# HackRPI-Badge.net
KiCad netlist of a schematic drawn in EAGLE
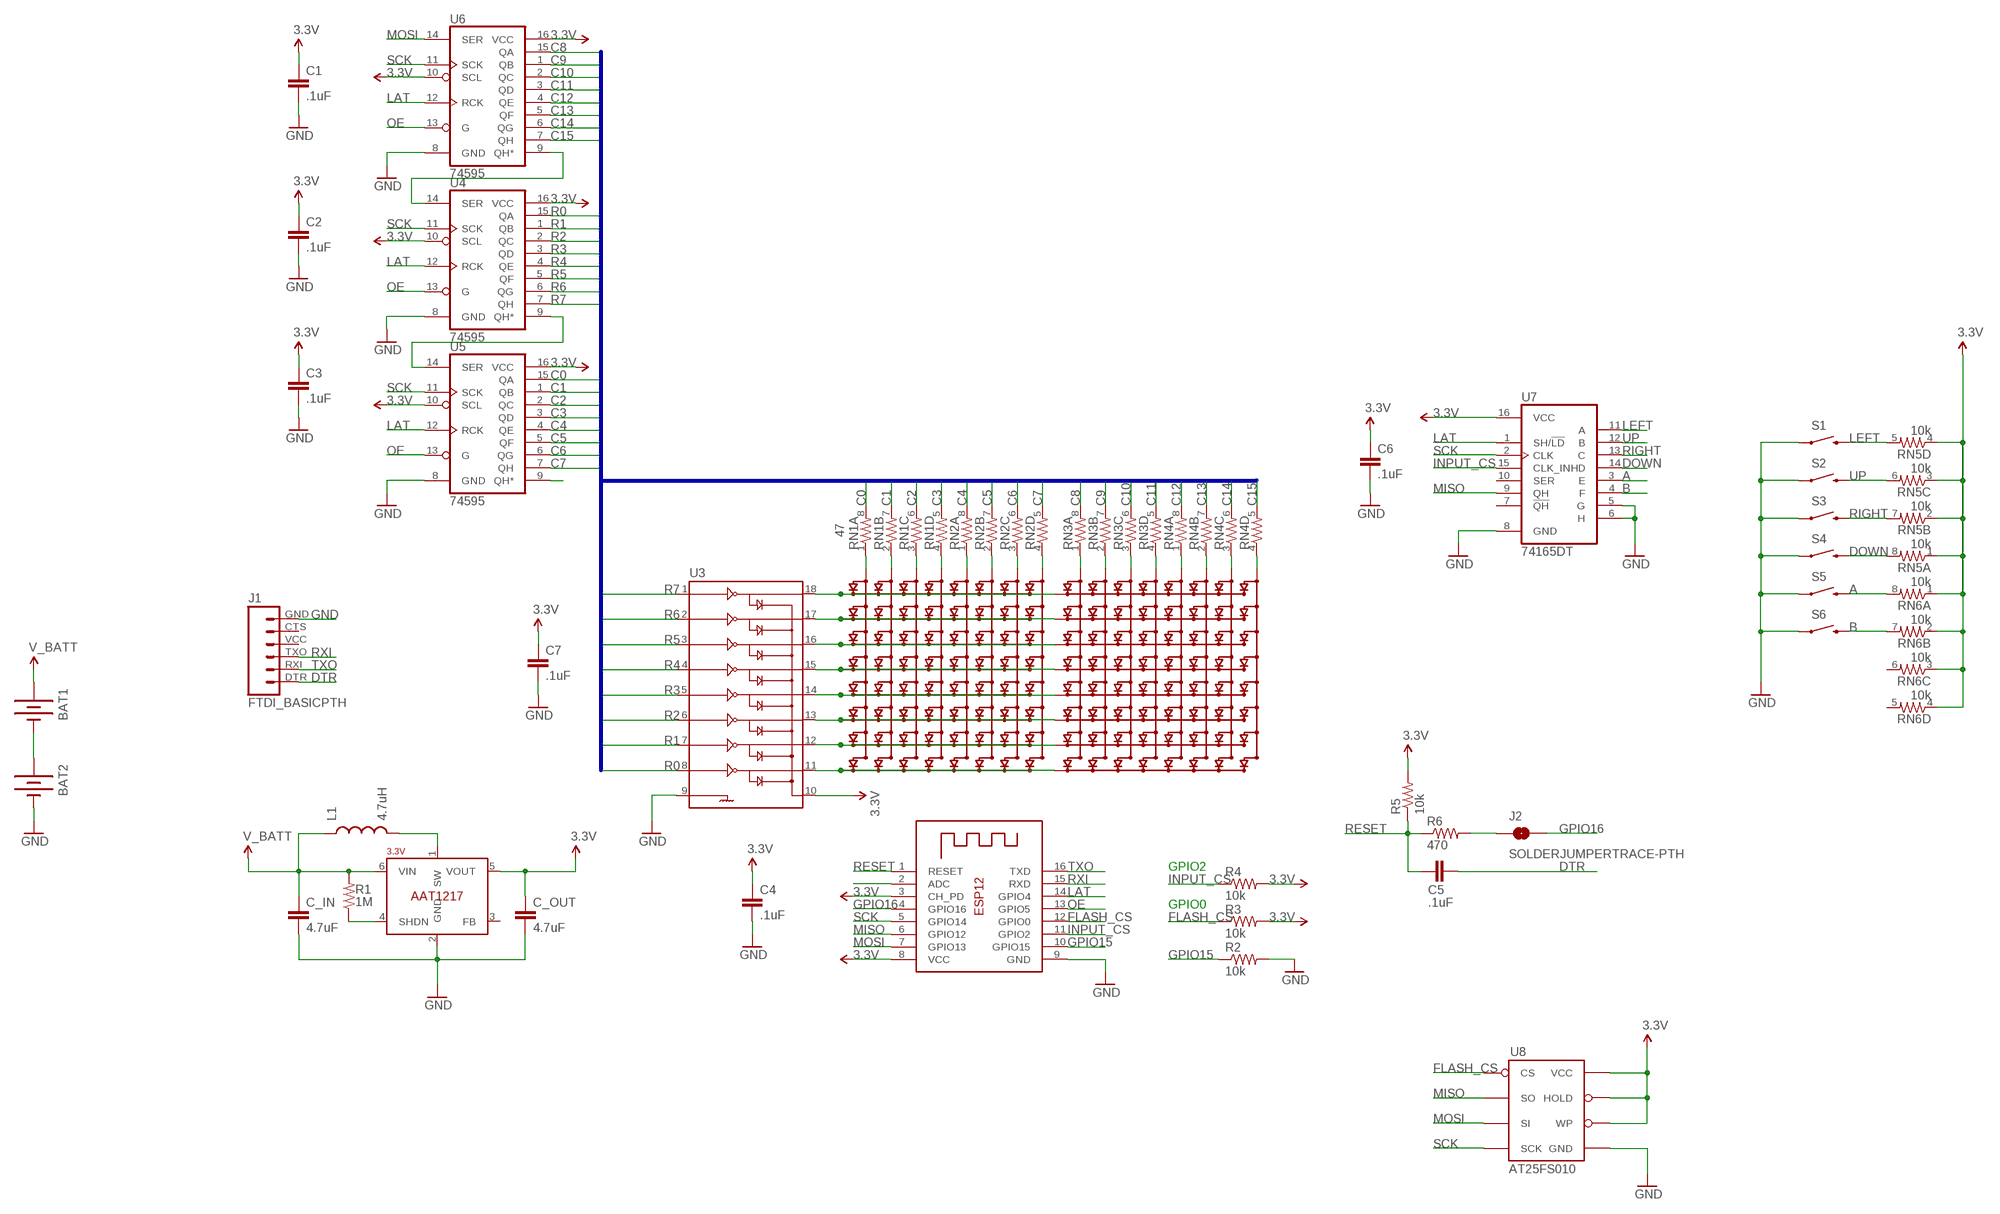
[diagram p0: schematic, sheet 1]

(export (version "E")
  (design (tool "Eeschema 10.0.6"))
  (components
    (comp (ref "BAT1")
      (value "BATTERYAAA")
      (footprint "eagle-import:BATTERY-AAA")
      (libsource (lib "eagle-import") (part "BATTERYAAA"))
    )
    (comp (ref "BAT2")
      (value "BATTERYAAA")
      (footprint "eagle-import:BATTERY-AAA")
      (libsource (lib "eagle-import") (part "BATTERYAAA"))
    )
    (comp (ref "C1")
      (value ".1uF")
      (footprint "eagle-import:0603-CAP")
      (libsource (lib "eagle-import") (part "CAP0603-CAP"))
    )
    (comp (ref "C2")
      (value ".1uF")
      (footprint "eagle-import:0603-CAP")
      (libsource (lib "eagle-import") (part "CAP0603-CAP"))
    )
    (comp (ref "C3")
      (value ".1uF")
      (footprint "eagle-import:0603-CAP")
      (libsource (lib "eagle-import") (part "CAP0603-CAP"))
    )
    (comp (ref "C4")
      (value ".1uF")
      (footprint "eagle-import:0603-CAP")
      (libsource (lib "eagle-import") (part "CAP0603-CAP"))
    )
    (comp (ref "C5")
      (value ".1uF")
      (footprint "eagle-import:0603-CAP")
      (libsource (lib "eagle-import") (part "CAP0603-CAP"))
    )
    (comp (ref "C6")
      (value ".1uF")
      (footprint "eagle-import:0603-CAP")
      (libsource (lib "eagle-import") (part "CAP0603-CAP"))
    )
    (comp (ref "C7")
      (value ".1uF")
      (footprint "eagle-import:0603-CAP")
      (libsource (lib "eagle-import") (part "CAP0603-CAP"))
    )
    (comp (ref "C_IN")
      (value "4.7uF")
      (footprint "eagle-import:0805")
      (libsource (lib "eagle-import") (part "CAP0805"))
    )
    (comp (ref "C_OUT")
      (value "4.7uF")
      (footprint "eagle-import:0805")
      (libsource (lib "eagle-import") (part "CAP0805"))
    )
    (comp (ref "J1")
      (value "FTDI_BASICPTH")
      (footprint "eagle-import:FTDI_BASIC")
      (libsource (lib "eagle-import") (part "FTDI_BASICPTH"))
    )
    (comp (ref "J2")
      (value "SOLDERJUMPERTRACE-PTH")
      (footprint "eagle-import:SJ_2S-TRACE-PTH")
      (libsource (lib "eagle-import") (part "SOLDERJUMPERTRACE-PTH"))
    )
    (comp (ref "L1")
      (value "4.7uH")
      (footprint "eagle-import:1007")
      (libsource (lib "eagle-import") (part "INDUCTOR1007"))
    )
    (comp (ref "LED_LEFT")
      (value "8X8LEDMATRIX_COLUMN_CATHODELDM-13488MI")
      (footprint "eagle-import:32MM_LEDMATRIX")
      (libsource (lib "eagle-import") (part "8X8LEDMATRIX_COLUMN_CATHODELDM-13488MI"))
    )
    (comp (ref "LEF_RIGHT")
      (value "8X8LEDMATRIX_COLUMN_CATHODELDM-13488MI")
      (footprint "eagle-import:32MM_LEDMATRIX")
      (libsource (lib "eagle-import") (part "8X8LEDMATRIX_COLUMN_CATHODELDM-13488MI"))
    )
    (comp (ref "R1")
      (value "1M")
      (footprint "eagle-import:0603-RES")
      (libsource (lib "eagle-import") (part "RESISTOR0603"))
    )
    (comp (ref "R2")
      (value "10k")
      (footprint "eagle-import:0603-RES")
      (libsource (lib "eagle-import") (part "RESISTOR0603"))
    )
    (comp (ref "R3")
      (value "10k")
      (footprint "eagle-import:0603-RES")
      (libsource (lib "eagle-import") (part "RESISTOR0603"))
    )
    (comp (ref "R4")
      (value "10k")
      (footprint "eagle-import:0603-RES")
      (libsource (lib "eagle-import") (part "RESISTOR0603"))
    )
    (comp (ref "R5")
      (value "10k")
      (footprint "eagle-import:0603-RES")
      (libsource (lib "eagle-import") (part "RESISTOR0603"))
    )
    (comp (ref "R6")
      (value "470")
      (footprint "eagle-import:0603-RES")
      (libsource (lib "eagle-import") (part "RESISTOR0603"))
    )
    (comp (ref "RN1")
      (value "47")
      (footprint "eagle-import:0603-ARV")
      (libsource (lib "eagle-import") (part "RESISTOR-ARRAY0603-ARV"))
    )
    (comp (ref "RN2")
      (value "47")
      (footprint "eagle-import:0603-ARV")
      (libsource (lib "eagle-import") (part "RESISTOR-ARRAY0603-ARV"))
    )
    (comp (ref "RN3")
      (value "47")
      (footprint "eagle-import:0603-ARV")
      (libsource (lib "eagle-import") (part "RESISTOR-ARRAY0603-ARV"))
    )
    (comp (ref "RN4")
      (value "47")
      (footprint "eagle-import:0603-ARV")
      (libsource (lib "eagle-import") (part "RESISTOR-ARRAY0603-ARV"))
    )
    (comp (ref "RN5")
      (value "10k")
      (footprint "eagle-import:0603-ARV")
      (libsource (lib "eagle-import") (part "RESISTOR-ARRAY0603-ARV"))
    )
    (comp (ref "RN6")
      (value "10k")
      (footprint "eagle-import:0603-ARV")
      (libsource (lib "eagle-import") (part "RESISTOR-ARRAY0603-ARV"))
    )
    (comp (ref "S1")
      (value "SWITCH-MOMENTARY-2PTH")
      (footprint "eagle-import:TACTILE-PTH")
      (libsource (lib "eagle-import") (part "SWITCH-MOMENTARY-2PTH"))
    )
    (comp (ref "S2")
      (value "SWITCH-MOMENTARY-2PTH")
      (footprint "eagle-import:TACTILE-PTH")
      (libsource (lib "eagle-import") (part "SWITCH-MOMENTARY-2PTH"))
    )
    (comp (ref "S3")
      (value "SWITCH-MOMENTARY-2PTH")
      (footprint "eagle-import:TACTILE-PTH")
      (libsource (lib "eagle-import") (part "SWITCH-MOMENTARY-2PTH"))
    )
    (comp (ref "S4")
      (value "SWITCH-MOMENTARY-2PTH")
      (footprint "eagle-import:TACTILE-PTH")
      (libsource (lib "eagle-import") (part "SWITCH-MOMENTARY-2PTH"))
    )
    (comp (ref "S5")
      (value "SWITCH-MOMENTARY-2PTH")
      (footprint "eagle-import:TACTILE-PTH")
      (libsource (lib "eagle-import") (part "SWITCH-MOMENTARY-2PTH"))
    )
    (comp (ref "S6")
      (value "SWITCH-MOMENTARY-2PTH")
      (footprint "eagle-import:TACTILE-PTH")
      (libsource (lib "eagle-import") (part "SWITCH-MOMENTARY-2PTH"))
    )
    (comp (ref "U1")
      (value "ESP-12")
      (footprint "eagle-import:ESP-12")
      (libsource (lib "eagle-import") (part "ESP-12"))
    )
    (comp (ref "U2")
      (value "3.3V")
      (footprint "eagle-import:SOT23-6")
      (libsource (lib "eagle-import") (part "AAT1217"))
    )
    (comp (ref "U3")
      (value "ULN2803SOICW")
      (footprint "eagle-import:SO18L")
      (libsource (lib "eagle-import") (part "ULN2803SOICW"))
    )
    (comp (ref "U4")
      (value "74595")
      (footprint "eagle-import:TSSOP16")
      (libsource (lib "eagle-import") (part "74595"))
    )
    (comp (ref "U5")
      (value "74595")
      (footprint "eagle-import:TSSOP16")
      (libsource (lib "eagle-import") (part "74595"))
    )
    (comp (ref "U6")
      (value "74595")
      (footprint "eagle-import:TSSOP16")
      (libsource (lib "eagle-import") (part "74595"))
    )
    (comp (ref "U7")
      (value "74165DT")
      (footprint "eagle-import:TSSOP16")
      (libsource (lib "eagle-import") (part "74165DT"))
    )
    (comp (ref "U8")
      (value "AT25FS010")
      (footprint "eagle-import:SO08WIDE")
      (libsource (lib "eagle-import") (part "AT25FS010"))
    )
  )
  (nets
    (net (code "1") (name "/A") (class "Default")
      (node (ref "RN6") (pin "8") (pinfunction "2_8") (pintype "passive"))
      (node (ref "S5") (pin "3") (pinfunction "2_3") (pintype "passive"))
      (node (ref "U7") (pin "3") (pinfunction "E_3") (pintype "tri_state"))
    )
    (net (code "2") (name "/B") (class "Default")
      (node (ref "RN6") (pin "7") (pinfunction "2_7") (pintype "passive"))
      (node (ref "S6") (pin "3") (pinfunction "2_3") (pintype "passive"))
      (node (ref "U7") (pin "4") (pinfunction "F_4") (pintype "tri_state"))
    )
    (net (code "3") (name "/C0") (class "Default")
      (node (ref "RN1") (pin "8") (pinfunction "2_8") (pintype "passive"))
      (node (ref "U5") (pin "15") (pinfunction "QA_15") (pintype "tri_state"))
    )
    (net (code "4") (name "/C1") (class "Default")
      (node (ref "RN1") (pin "7") (pinfunction "2_7") (pintype "passive"))
      (node (ref "U5") (pin "1") (pinfunction "QB_1") (pintype "tri_state"))
    )
    (net (code "5") (name "/C2") (class "Default")
      (node (ref "RN1") (pin "6") (pinfunction "2_6") (pintype "passive"))
      (node (ref "U5") (pin "2") (pinfunction "QC_2") (pintype "tri_state"))
    )
    (net (code "6") (name "/C3") (class "Default")
      (node (ref "RN1") (pin "5") (pinfunction "2_5") (pintype "passive"))
      (node (ref "U5") (pin "3") (pinfunction "QD_3") (pintype "tri_state"))
    )
    (net (code "7") (name "/C4") (class "Default")
      (node (ref "RN2") (pin "8") (pinfunction "2_8") (pintype "passive"))
      (node (ref "U5") (pin "4") (pinfunction "QE_4") (pintype "tri_state"))
    )
    (net (code "8") (name "/C5") (class "Default")
      (node (ref "RN2") (pin "7") (pinfunction "2_7") (pintype "passive"))
      (node (ref "U5") (pin "5") (pinfunction "QF_5") (pintype "tri_state"))
    )
    (net (code "9") (name "/C6") (class "Default")
      (node (ref "RN2") (pin "6") (pinfunction "2_6") (pintype "passive"))
      (node (ref "U5") (pin "6") (pinfunction "QG_6") (pintype "tri_state"))
    )
    (net (code "10") (name "/C7") (class "Default")
      (node (ref "RN2") (pin "5") (pinfunction "2_5") (pintype "passive"))
      (node (ref "U5") (pin "7") (pinfunction "QH_7") (pintype "tri_state"))
    )
    (net (code "11") (name "/C8") (class "Default")
      (node (ref "RN3") (pin "8") (pinfunction "2_8") (pintype "passive"))
      (node (ref "U6") (pin "15") (pinfunction "QA_15") (pintype "tri_state"))
    )
    (net (code "12") (name "/C9") (class "Default")
      (node (ref "RN3") (pin "7") (pinfunction "2_7") (pintype "passive"))
      (node (ref "U6") (pin "1") (pinfunction "QB_1") (pintype "tri_state"))
    )
    (net (code "13") (name "/C10") (class "Default")
      (node (ref "RN3") (pin "6") (pinfunction "2_6") (pintype "passive"))
      (node (ref "U6") (pin "2") (pinfunction "QC_2") (pintype "tri_state"))
    )
    (net (code "14") (name "/C11") (class "Default")
      (node (ref "RN3") (pin "5") (pinfunction "2_5") (pintype "passive"))
      (node (ref "U6") (pin "3") (pinfunction "QD_3") (pintype "tri_state"))
    )
    (net (code "15") (name "/C12") (class "Default")
      (node (ref "RN4") (pin "8") (pinfunction "2_8") (pintype "passive"))
      (node (ref "U6") (pin "4") (pinfunction "QE_4") (pintype "tri_state"))
    )
    (net (code "16") (name "/C13") (class "Default")
      (node (ref "RN4") (pin "7") (pinfunction "2_7") (pintype "passive"))
      (node (ref "U6") (pin "5") (pinfunction "QF_5") (pintype "tri_state"))
    )
    (net (code "17") (name "/C14") (class "Default")
      (node (ref "RN4") (pin "6") (pinfunction "2_6") (pintype "passive"))
      (node (ref "U6") (pin "6") (pinfunction "QG_6") (pintype "tri_state"))
    )
    (net (code "18") (name "/C15") (class "Default")
      (node (ref "RN4") (pin "5") (pinfunction "2_5") (pintype "passive"))
      (node (ref "U6") (pin "7") (pinfunction "QH_7") (pintype "tri_state"))
    )
    (net (code "19") (name "/DOWN") (class "Default")
      (node (ref "RN5") (pin "8") (pinfunction "2_8") (pintype "passive"))
      (node (ref "S4") (pin "3") (pinfunction "2_3") (pintype "passive"))
      (node (ref "U7") (pin "14") (pinfunction "D_14") (pintype "tri_state"))
    )
    (net (code "20") (name "/DTR") (class "Default")
      (node (ref "C5") (pin "2") (pinfunction "2_2") (pintype "passive"))
      (node (ref "J1") (pin "DTR") (pinfunction "1_DTR") (pintype "passive"))
    )
    (net (code "21") (name "/FLASH_CS") (class "Default")
      (node (ref "R3") (pin "1") (pinfunction "1_1") (pintype "passive"))
      (node (ref "U1") (pin "12") (pinfunction "GPIO0_12") (pintype "bidirectional"))
      (node (ref "U8") (pin "1") (pinfunction "CS_1") (pintype "bidirectional"))
    )
    (net (code "22") (name "/GPIO15") (class "Default")
      (node (ref "R2") (pin "1") (pinfunction "1_1") (pintype "passive"))
      (node (ref "U1") (pin "10") (pinfunction "GPIO15_10") (pintype "bidirectional"))
    )
    (net (code "23") (name "/GPIO16") (class "Default")
      (node (ref "J2") (pin "2") (pinfunction "2_2") (pintype "passive"))
      (node (ref "U1") (pin "4") (pinfunction "GPIO16_4") (pintype "bidirectional"))
    )
    (net (code "24") (name "/INPUT_CS") (class "Default")
      (node (ref "R4") (pin "1") (pinfunction "1_1") (pintype "passive"))
      (node (ref "U1") (pin "11") (pinfunction "GPIO2_11") (pintype "bidirectional"))
      (node (ref "U7") (pin "15") (pinfunction "CLK_INH_15") (pintype "input"))
    )
    (net (code "25") (name "/LAT") (class "Default")
      (node (ref "U1") (pin "14") (pinfunction "GPIO4_14") (pintype "bidirectional"))
      (node (ref "U4") (pin "12") (pinfunction "RCK_12") (pintype "input"))
      (node (ref "U5") (pin "12") (pinfunction "RCK_12") (pintype "input"))
      (node (ref "U6") (pin "12") (pinfunction "RCK_12") (pintype "input"))
      (node (ref "U7") (pin "1") (pinfunction "SH/~{LD}_1") (pintype "input"))
    )
    (net (code "26") (name "/LEFT") (class "Default")
      (node (ref "RN5") (pin "5") (pinfunction "2_5") (pintype "passive"))
      (node (ref "S1") (pin "3") (pinfunction "2_3") (pintype "passive"))
      (node (ref "U7") (pin "11") (pinfunction "A_11") (pintype "tri_state"))
    )
    (net (code "27") (name "/MISO") (class "Default")
      (node (ref "U1") (pin "6") (pinfunction "GPIO12_6") (pintype "bidirectional"))
      (node (ref "U7") (pin "9") (pinfunction "QH_9") (pintype "tri_state"))
      (node (ref "U8") (pin "2") (pinfunction "SO_2") (pintype "bidirectional"))
    )
    (net (code "28") (name "/MOSI") (class "Default")
      (node (ref "U1") (pin "7") (pinfunction "GPIO13_7") (pintype "bidirectional"))
      (node (ref "U6") (pin "14") (pinfunction "SER_14") (pintype "input"))
      (node (ref "U8") (pin "5") (pinfunction "SI_5") (pintype "bidirectional"))
    )
    (net (code "29") (name "/OE") (class "Default")
      (node (ref "U1") (pin "13") (pinfunction "GPIO5_13") (pintype "bidirectional"))
      (node (ref "U4") (pin "13") (pinfunction "G_13") (pintype "input"))
      (node (ref "U5") (pin "13") (pinfunction "G_13") (pintype "input"))
      (node (ref "U6") (pin "13") (pinfunction "G_13") (pintype "input"))
    )
    (net (code "30") (name "/R0") (class "Default")
      (node (ref "U3") (pin "8") (pinfunction "8_8") (pintype "bidirectional"))
      (node (ref "U4") (pin "15") (pinfunction "QA_15") (pintype "tri_state"))
    )
    (net (code "31") (name "/R1") (class "Default")
      (node (ref "U3") (pin "7") (pinfunction "7_7") (pintype "bidirectional"))
      (node (ref "U4") (pin "1") (pinfunction "QB_1") (pintype "tri_state"))
    )
    (net (code "32") (name "/R2") (class "Default")
      (node (ref "U3") (pin "6") (pinfunction "6_6") (pintype "bidirectional"))
      (node (ref "U4") (pin "2") (pinfunction "QC_2") (pintype "tri_state"))
    )
    (net (code "33") (name "/R3") (class "Default")
      (node (ref "U3") (pin "5") (pinfunction "5_5") (pintype "bidirectional"))
      (node (ref "U4") (pin "3") (pinfunction "QD_3") (pintype "tri_state"))
    )
    (net (code "34") (name "/R4") (class "Default")
      (node (ref "U3") (pin "4") (pinfunction "4_4") (pintype "bidirectional"))
      (node (ref "U4") (pin "4") (pinfunction "QE_4") (pintype "tri_state"))
    )
    (net (code "35") (name "/R5") (class "Default")
      (node (ref "U3") (pin "3") (pinfunction "3_3") (pintype "bidirectional"))
      (node (ref "U4") (pin "5") (pinfunction "QF_5") (pintype "tri_state"))
    )
    (net (code "36") (name "/R6") (class "Default")
      (node (ref "U3") (pin "2") (pinfunction "2_2") (pintype "bidirectional"))
      (node (ref "U4") (pin "6") (pinfunction "QG_6") (pintype "tri_state"))
    )
    (net (code "37") (name "/R7") (class "Default")
      (node (ref "U3") (pin "1") (pinfunction "1_1") (pintype "bidirectional"))
      (node (ref "U4") (pin "7") (pinfunction "QH_7") (pintype "tri_state"))
    )
    (net (code "38") (name "/RESET") (class "Default")
      (node (ref "C5") (pin "1") (pinfunction "1_1") (pintype "passive"))
      (node (ref "R5") (pin "1") (pinfunction "1_1") (pintype "passive"))
      (node (ref "R6") (pin "1") (pinfunction "1_1") (pintype "passive"))
      (node (ref "U1") (pin "1") (pinfunction "RESET_1") (pintype "input"))
    )
    (net (code "39") (name "/RIGHT") (class "Default")
      (node (ref "RN5") (pin "7") (pinfunction "2_7") (pintype "passive"))
      (node (ref "S3") (pin "3") (pinfunction "2_3") (pintype "passive"))
      (node (ref "U7") (pin "13") (pinfunction "C_13") (pintype "tri_state"))
    )
    (net (code "40") (name "/RXI") (class "Default")
      (node (ref "J1") (pin "TXO") (pinfunction "3_TXO") (pintype "passive"))
      (node (ref "U1") (pin "15") (pinfunction "RXD_15") (pintype "input"))
    )
    (net (code "41") (name "/SCK") (class "Default")
      (node (ref "U1") (pin "5") (pinfunction "GPIO14_5") (pintype "bidirectional"))
      (node (ref "U4") (pin "11") (pinfunction "SCK_11") (pintype "input"))
      (node (ref "U5") (pin "11") (pinfunction "SCK_11") (pintype "input"))
      (node (ref "U6") (pin "11") (pinfunction "SCK_11") (pintype "input"))
      (node (ref "U7") (pin "2") (pinfunction "CLK_2") (pintype "input"))
      (node (ref "U8") (pin "6") (pinfunction "SCK_6") (pintype "bidirectional"))
    )
    (net (code "42") (name "/TXO") (class "Default")
      (node (ref "J1") (pin "RXI") (pinfunction "2_RXI") (pintype "passive"))
      (node (ref "U1") (pin "16") (pinfunction "TXD_16") (pintype "output"))
    )
    (net (code "43") (name "/UP") (class "Default")
      (node (ref "RN5") (pin "6") (pinfunction "2_6") (pintype "passive"))
      (node (ref "S2") (pin "3") (pinfunction "2_3") (pintype "passive"))
      (node (ref "U7") (pin "12") (pinfunction "B_12") (pintype "tri_state"))
    )
    (net (code "44") (name "3.3V") (class "Default")
      (node (ref "C1") (pin "1") (pinfunction "1_1") (pintype "passive"))
      (node (ref "C2") (pin "1") (pinfunction "1_1") (pintype "passive"))
      (node (ref "C3") (pin "1") (pinfunction "1_1") (pintype "passive"))
      (node (ref "C4") (pin "1") (pinfunction "1_1") (pintype "passive"))
      (node (ref "C6") (pin "1") (pinfunction "1_1") (pintype "passive"))
      (node (ref "C7") (pin "1") (pinfunction "1_1") (pintype "passive"))
      (node (ref "C_OUT") (pin "1") (pinfunction "1_1") (pintype "passive"))
      (node (ref "R3") (pin "2") (pinfunction "2_2") (pintype "passive"))
      (node (ref "R4") (pin "2") (pinfunction "2_2") (pintype "passive"))
      (node (ref "R5") (pin "2") (pinfunction "2_2") (pintype "passive"))
      (node (ref "RN5") (pin "1") (pinfunction "1_1") (pintype "passive"))
      (node (ref "RN5") (pin "2") (pinfunction "1_2") (pintype "passive"))
      (node (ref "RN5") (pin "3") (pinfunction "1_3") (pintype "passive"))
      (node (ref "RN5") (pin "4") (pinfunction "1_4") (pintype "passive"))
      (node (ref "RN6") (pin "1") (pinfunction "1_1") (pintype "passive"))
      (node (ref "RN6") (pin "2") (pinfunction "1_2") (pintype "passive"))
      (node (ref "RN6") (pin "3") (pinfunction "1_3") (pintype "passive"))
      (node (ref "RN6") (pin "4") (pinfunction "1_4") (pintype "passive"))
      (node (ref "U1") (pin "3") (pinfunction "CH_PD_3") (pintype "input"))
      (node (ref "U1") (pin "8") (pinfunction "VCC_8") (pintype "power_in"))
      (node (ref "U2") (pin "5") (pinfunction "VOUT_5") (pintype "power_in"))
      (node (ref "U3") (pin "10") (pinfunction "10_10") (pintype "bidirectional"))
      (node (ref "U4") (pin "10") (pinfunction "SCL_10") (pintype "input"))
      (node (ref "U4") (pin "16") (pinfunction "VCC_16") (pintype "power_in"))
      (node (ref "U5") (pin "10") (pinfunction "SCL_10") (pintype "input"))
      (node (ref "U5") (pin "16") (pinfunction "VCC_16") (pintype "power_in"))
      (node (ref "U6") (pin "10") (pinfunction "SCL_10") (pintype "input"))
      (node (ref "U6") (pin "16") (pinfunction "VCC_16") (pintype "power_in"))
      (node (ref "U7") (pin "16") (pinfunction "VCC_16") (pintype "power_in"))
      (node (ref "U8") (pin "3") (pinfunction "WP_3") (pintype "bidirectional"))
      (node (ref "U8") (pin "7") (pinfunction "HOLD_7") (pintype "bidirectional"))
      (node (ref "U8") (pin "8") (pinfunction "VCC_8") (pintype "bidirectional"))
    )
    (net (code "45") (name "GND") (class "Default")
      (node (ref "BAT2") (pin "GND@1") (pinfunction "-_GND@1") (pintype "power_in"))
      (node (ref "C1") (pin "2") (pinfunction "2_2") (pintype "passive"))
      (node (ref "C2") (pin "2") (pinfunction "2_2") (pintype "passive"))
      (node (ref "C3") (pin "2") (pinfunction "2_2") (pintype "passive"))
      (node (ref "C4") (pin "2") (pinfunction "2_2") (pintype "passive"))
      (node (ref "C6") (pin "2") (pinfunction "2_2") (pintype "passive"))
      (node (ref "C7") (pin "2") (pinfunction "2_2") (pintype "passive"))
      (node (ref "C_IN") (pin "2") (pinfunction "2_2") (pintype "passive"))
      (node (ref "C_OUT") (pin "2") (pinfunction "2_2") (pintype "passive"))
      (node (ref "J1") (pin "GND") (pinfunction "6_GND") (pintype "passive"))
      (node (ref "R2") (pin "2") (pinfunction "2_2") (pintype "passive"))
      (node (ref "S1") (pin "1") (pinfunction "1_1") (pintype "passive"))
      (node (ref "S2") (pin "1") (pinfunction "1_1") (pintype "passive"))
      (node (ref "S3") (pin "1") (pinfunction "1_1") (pintype "passive"))
      (node (ref "S4") (pin "1") (pinfunction "1_1") (pintype "passive"))
      (node (ref "S5") (pin "1") (pinfunction "1_1") (pintype "passive"))
      (node (ref "S6") (pin "1") (pinfunction "1_1") (pintype "passive"))
      (node (ref "U1") (pin "9") (pinfunction "GND_9") (pintype "power_in"))
      (node (ref "U2") (pin "2") (pinfunction "GND_2") (pintype "power_in"))
      (node (ref "U3") (pin "9") (pinfunction "9_9") (pintype "bidirectional"))
      (node (ref "U4") (pin "8") (pinfunction "GND_8") (pintype "power_in"))
      (node (ref "U5") (pin "8") (pinfunction "GND_8") (pintype "power_in"))
      (node (ref "U6") (pin "8") (pinfunction "GND_8") (pintype "power_in"))
      (node (ref "U7") (pin "5") (pinfunction "G_5") (pintype "tri_state"))
      (node (ref "U7") (pin "6") (pinfunction "H_6") (pintype "tri_state"))
      (node (ref "U7") (pin "8") (pinfunction "GND_8") (pintype "power_in"))
      (node (ref "U8") (pin "4") (pinfunction "GND_4") (pintype "bidirectional"))
    )
    (net (code "46") (name "Net-(BAT1--)") (class "Default")
      (node (ref "BAT1") (pin "GND@1") (pinfunction "-_GND@1") (pintype "power_in"))
      (node (ref "BAT2") (pin "PWR@1") (pinfunction "+_PWR@1") (pintype "power_in"))
    )
    (net (code "47") (name "Net-(J2-Pad1)") (class "Default")
      (node (ref "J2") (pin "1") (pinfunction "1_1") (pintype "passive"))
      (node (ref "R6") (pin "2") (pinfunction "2_2") (pintype "passive"))
    )
    (net (code "48") (name "Net-(LED_LEFT-C1)") (class "Default")
      (node (ref "LED_LEFT") (pin "13") (pinfunction "C1_13") (pintype "bidirectional"))
      (node (ref "RN1") (pin "1") (pinfunction "1_1") (pintype "passive"))
    )
    (net (code "49") (name "Net-(LED_LEFT-C2)") (class "Default")
      (node (ref "LED_LEFT") (pin "3") (pinfunction "C2_3") (pintype "bidirectional"))
      (node (ref "RN1") (pin "2") (pinfunction "1_2") (pintype "passive"))
    )
    (net (code "50") (name "Net-(LED_LEFT-C3)") (class "Default")
      (node (ref "LED_LEFT") (pin "4") (pinfunction "C3_4") (pintype "bidirectional"))
      (node (ref "RN1") (pin "3") (pinfunction "1_3") (pintype "passive"))
    )
    (net (code "51") (name "Net-(LED_LEFT-C4)") (class "Default")
      (node (ref "LED_LEFT") (pin "10") (pinfunction "C4_10") (pintype "bidirectional"))
      (node (ref "RN1") (pin "4") (pinfunction "1_4") (pintype "passive"))
    )
    (net (code "52") (name "Net-(LED_LEFT-C5)") (class "Default")
      (node (ref "LED_LEFT") (pin "6") (pinfunction "C5_6") (pintype "bidirectional"))
      (node (ref "RN2") (pin "1") (pinfunction "1_1") (pintype "passive"))
    )
    (net (code "53") (name "Net-(LED_LEFT-C6)") (class "Default")
      (node (ref "LED_LEFT") (pin "11") (pinfunction "C6_11") (pintype "bidirectional"))
      (node (ref "RN2") (pin "2") (pinfunction "1_2") (pintype "passive"))
    )
    (net (code "54") (name "Net-(LED_LEFT-C7)") (class "Default")
      (node (ref "LED_LEFT") (pin "15") (pinfunction "C7_15") (pintype "bidirectional"))
      (node (ref "RN2") (pin "3") (pinfunction "1_3") (pintype "passive"))
    )
    (net (code "55") (name "Net-(LED_LEFT-C8)") (class "Default")
      (node (ref "LED_LEFT") (pin "16") (pinfunction "C8_16") (pintype "bidirectional"))
      (node (ref "RN2") (pin "4") (pinfunction "1_4") (pintype "passive"))
    )
    (net (code "56") (name "Net-(LED_LEFT-R1)") (class "Default")
      (node (ref "LED_LEFT") (pin "9") (pinfunction "R1_9") (pintype "bidirectional"))
      (node (ref "LEF_RIGHT") (pin "9") (pinfunction "R1_9") (pintype "bidirectional"))
      (node (ref "U3") (pin "18") (pinfunction "18_18") (pintype "bidirectional"))
    )
    (net (code "57") (name "Net-(LED_LEFT-R2)") (class "Default")
      (node (ref "LED_LEFT") (pin "14") (pinfunction "R2_14") (pintype "bidirectional"))
      (node (ref "LEF_RIGHT") (pin "14") (pinfunction "R2_14") (pintype "bidirectional"))
      (node (ref "U3") (pin "17") (pinfunction "17_17") (pintype "bidirectional"))
    )
    (net (code "58") (name "Net-(LED_LEFT-R3)") (class "Default")
      (node (ref "LED_LEFT") (pin "8") (pinfunction "R3_8") (pintype "bidirectional"))
      (node (ref "LEF_RIGHT") (pin "8") (pinfunction "R3_8") (pintype "bidirectional"))
      (node (ref "U3") (pin "16") (pinfunction "16_16") (pintype "bidirectional"))
    )
    (net (code "59") (name "Net-(LED_LEFT-R4)") (class "Default")
      (node (ref "LED_LEFT") (pin "12") (pinfunction "R4_12") (pintype "bidirectional"))
      (node (ref "LEF_RIGHT") (pin "12") (pinfunction "R4_12") (pintype "bidirectional"))
      (node (ref "U3") (pin "15") (pinfunction "15_15") (pintype "bidirectional"))
    )
    (net (code "60") (name "Net-(LED_LEFT-R5)") (class "Default")
      (node (ref "LED_LEFT") (pin "1") (pinfunction "R5_1") (pintype "bidirectional"))
      (node (ref "LEF_RIGHT") (pin "1") (pinfunction "R5_1") (pintype "bidirectional"))
      (node (ref "U3") (pin "14") (pinfunction "14_14") (pintype "bidirectional"))
    )
    (net (code "61") (name "Net-(LED_LEFT-R6)") (class "Default")
      (node (ref "LED_LEFT") (pin "7") (pinfunction "R6_7") (pintype "bidirectional"))
      (node (ref "LEF_RIGHT") (pin "7") (pinfunction "R6_7") (pintype "bidirectional"))
      (node (ref "U3") (pin "13") (pinfunction "13_13") (pintype "bidirectional"))
    )
    (net (code "62") (name "Net-(LED_LEFT-R7)") (class "Default")
      (node (ref "LED_LEFT") (pin "2") (pinfunction "R7_2") (pintype "bidirectional"))
      (node (ref "LEF_RIGHT") (pin "2") (pinfunction "R7_2") (pintype "bidirectional"))
      (node (ref "U3") (pin "12") (pinfunction "12_12") (pintype "bidirectional"))
    )
    (net (code "63") (name "Net-(LED_LEFT-R8)") (class "Default")
      (node (ref "LED_LEFT") (pin "5") (pinfunction "R8_5") (pintype "bidirectional"))
      (node (ref "LEF_RIGHT") (pin "5") (pinfunction "R8_5") (pintype "bidirectional"))
      (node (ref "U3") (pin "11") (pinfunction "11_11") (pintype "bidirectional"))
    )
    (net (code "64") (name "Net-(LEF_RIGHT-C1)") (class "Default")
      (node (ref "LEF_RIGHT") (pin "13") (pinfunction "C1_13") (pintype "bidirectional"))
      (node (ref "RN3") (pin "1") (pinfunction "1_1") (pintype "passive"))
    )
    (net (code "65") (name "Net-(LEF_RIGHT-C2)") (class "Default")
      (node (ref "LEF_RIGHT") (pin "3") (pinfunction "C2_3") (pintype "bidirectional"))
      (node (ref "RN3") (pin "2") (pinfunction "1_2") (pintype "passive"))
    )
    (net (code "66") (name "Net-(LEF_RIGHT-C3)") (class "Default")
      (node (ref "LEF_RIGHT") (pin "4") (pinfunction "C3_4") (pintype "bidirectional"))
      (node (ref "RN3") (pin "3") (pinfunction "1_3") (pintype "passive"))
    )
    (net (code "67") (name "Net-(LEF_RIGHT-C4)") (class "Default")
      (node (ref "LEF_RIGHT") (pin "10") (pinfunction "C4_10") (pintype "bidirectional"))
      (node (ref "RN3") (pin "4") (pinfunction "1_4") (pintype "passive"))
    )
    (net (code "68") (name "Net-(LEF_RIGHT-C5)") (class "Default")
      (node (ref "LEF_RIGHT") (pin "6") (pinfunction "C5_6") (pintype "bidirectional"))
      (node (ref "RN4") (pin "1") (pinfunction "1_1") (pintype "passive"))
    )
    (net (code "69") (name "Net-(LEF_RIGHT-C6)") (class "Default")
      (node (ref "LEF_RIGHT") (pin "11") (pinfunction "C6_11") (pintype "bidirectional"))
      (node (ref "RN4") (pin "2") (pinfunction "1_2") (pintype "passive"))
    )
    (net (code "70") (name "Net-(LEF_RIGHT-C7)") (class "Default")
      (node (ref "LEF_RIGHT") (pin "15") (pinfunction "C7_15") (pintype "bidirectional"))
      (node (ref "RN4") (pin "3") (pinfunction "1_3") (pintype "passive"))
    )
    (net (code "71") (name "Net-(LEF_RIGHT-C8)") (class "Default")
      (node (ref "LEF_RIGHT") (pin "16") (pinfunction "C8_16") (pintype "bidirectional"))
      (node (ref "RN4") (pin "4") (pinfunction "1_4") (pintype "passive"))
    )
    (net (code "72") (name "Net-(U2-SHDN)") (class "Default")
      (node (ref "R1") (pin "1") (pinfunction "1_1") (pintype "passive"))
      (node (ref "U2") (pin "4") (pinfunction "SHDN_4") (pintype "input"))
    )
    (net (code "73") (name "Net-(U2-SW)") (class "Default")
      (node (ref "L1") (pin "2") (pinfunction "2_2") (pintype "passive"))
      (node (ref "U2") (pin "1") (pinfunction "SW_1") (pintype "input"))
    )
    (net (code "74") (name "Net-(U4-QH*)") (class "Default")
      (node (ref "U4") (pin "9") (pinfunction "QH*_9") (pintype "tri_state"))
      (node (ref "U5") (pin "14") (pinfunction "SER_14") (pintype "input"))
    )
    (net (code "75") (name "Net-(U4-SER)") (class "Default")
      (node (ref "U4") (pin "14") (pinfunction "SER_14") (pintype "input"))
      (node (ref "U6") (pin "9") (pinfunction "QH*_9") (pintype "tri_state"))
    )
    (net (code "76") (name "V_BATT") (class "Default")
      (node (ref "BAT1") (pin "PWR@1") (pinfunction "+_PWR@1") (pintype "power_in"))
      (node (ref "C_IN") (pin "1") (pinfunction "1_1") (pintype "passive"))
      (node (ref "L1") (pin "1") (pinfunction "1_1") (pintype "passive"))
      (node (ref "R1") (pin "2") (pinfunction "2_2") (pintype "passive"))
      (node (ref "U2") (pin "6") (pinfunction "VIN_6") (pintype "power_in"))
    )
    (net (code "77") (name "unconnected-(J1-4-PadVCC)") (class "Default")
      (node (ref "J1") (pin "VCC") (pinfunction "4_VCC") (pintype "passive"))
    )
    (net (code "78") (name "unconnected-(J1-5-PadCTS)") (class "Default")
      (node (ref "J1") (pin "CTS") (pinfunction "5_CTS") (pintype "passive"))
    )
    (net (code "79") (name "unconnected-(RN6C-2-Pad6)") (class "Default")
      (node (ref "RN6") (pin "6") (pinfunction "2_6") (pintype "passive"))
    )
    (net (code "80") (name "unconnected-(RN6D-2-Pad5)") (class "Default")
      (node (ref "RN6") (pin "5") (pinfunction "2_5") (pintype "passive"))
    )
    (net (code "81") (name "unconnected-(U1-ADC-Pad2)") (class "Default")
      (node (ref "U1") (pin "2") (pinfunction "ADC_2") (pintype "passive"))
    )
    (net (code "82") (name "unconnected-(U2-FB-Pad3)") (class "Default")
      (node (ref "U2") (pin "3") (pinfunction "FB_3") (pintype "input"))
    )
    (net (code "83") (name "unconnected-(U5-QH*-Pad9)") (class "Default")
      (node (ref "U5") (pin "9") (pinfunction "QH*_9") (pintype "tri_state"))
    )
    (net (code "84") (name "unconnected-(U7-SER-Pad10)") (class "Default")
      (node (ref "U7") (pin "10") (pinfunction "SER_10") (pintype "input"))
    )
    (net (code "85") (name "unconnected-(U7-~{QH}-Pad7)") (class "Default")
      (node (ref "U7") (pin "7") (pinfunction "~{QH}_7") (pintype "input"))
    )
  )
)
